# CAN.net
KiCad netlist of a schematic drawn in Altium Designer
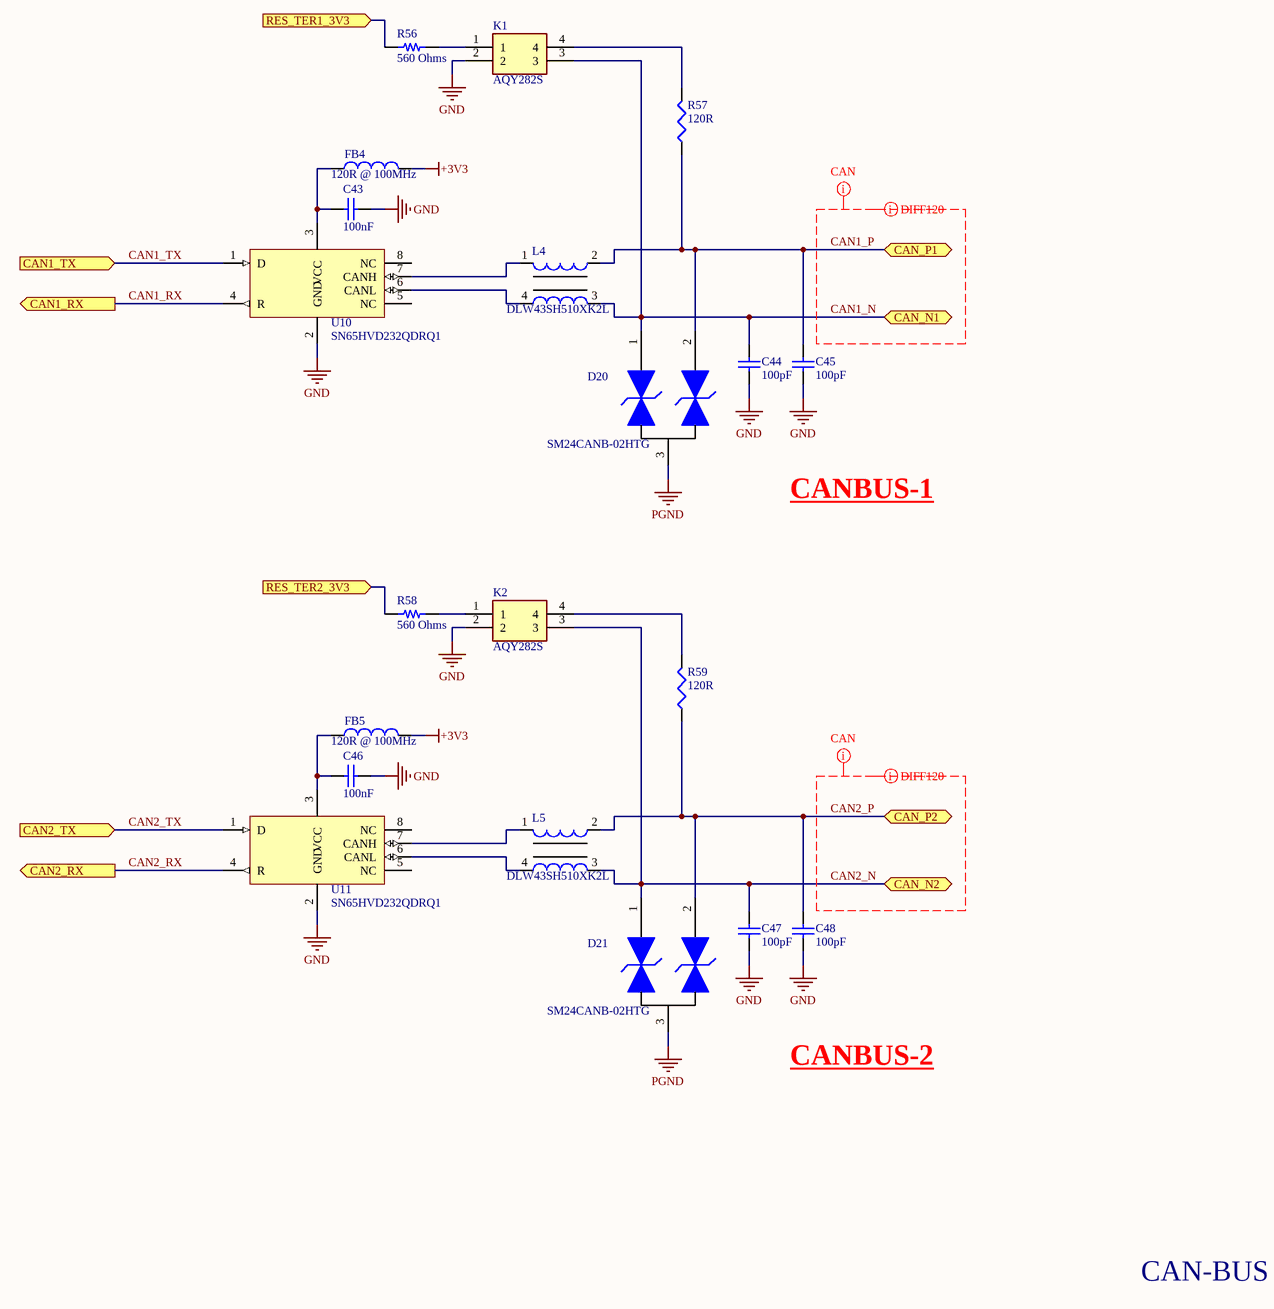
[diagram p0: CAN.SchDoc]

(export (version "E")
  (design (tool "Eeschema 10.0.6"))
  (components
    (comp (ref "C43")
      (value "100nF")
      (footprint "CAP0603")
      (description "CAP CER 0.1UF 50V X7R 0603")
      (libsource (lib "CAP_Library") (part "CAP0603_100nF"))
    )
    (comp (ref "C44")
      (value "100pF")
      (footprint "CAP0603")
      (description "CAP CER 100PF 50V C0G/NP0 0603")
      (libsource (lib "CAP_Library") (part "CAP0603_100pF"))
    )
    (comp (ref "C45")
      (value "100pF")
      (footprint "CAP0603")
      (description "CAP CER 100PF 50V C0G/NP0 0603")
      (libsource (lib "CAP_Library") (part "CAP0603_100pF"))
    )
    (comp (ref "C46")
      (value "100nF")
      (footprint "CAP0603")
      (description "CAP CER 0.1UF 50V X7R 0603")
      (libsource (lib "CAP_Library") (part "CAP0603_100nF"))
    )
    (comp (ref "C47")
      (value "100pF")
      (footprint "CAP0603")
      (description "CAP CER 100PF 50V C0G/NP0 0603")
      (libsource (lib "CAP_Library") (part "CAP0603_100pF"))
    )
    (comp (ref "C48")
      (value "100pF")
      (footprint "CAP0603")
      (description "CAP CER 100PF 50V C0G/NP0 0603")
      (libsource (lib "CAP_Library") (part "CAP0603_100pF"))
    )
    (comp (ref "D20")
      (value "CAN")
      (footprint "SOT23_3-DIODE")
      (description "TVS DIODE 24VWM 50VC SOT23-3")
      (fields (field (name "P/N") "SM24CANB-02HTG"))
      (libsource (lib "DIODE_Library") (part "SM24CANB-02HTG_TVS"))
    )
    (comp (ref "D21")
      (value "CAN")
      (footprint "SOT23_3-DIODE")
      (description "TVS DIODE 24VWM 50VC SOT23-3")
      (fields (field (name "P/N") "SM24CANB-02HTG"))
      (libsource (lib "DIODE_Library") (part "SM24CANB-02HTG_TVS"))
    )
    (comp (ref "FB4")
      (value "120R @ 100MHz")
      (footprint "FB0603")
      (description "FERRITE BEAD 120 OHM 0603 1LN")
      (libsource (lib "FB_Library") (part "FB0603_120R@100MHz"))
    )
    (comp (ref "FB5")
      (value "120R @ 100MHz")
      (footprint "FB0603")
      (description "FERRITE BEAD 120 OHM 0603 1LN")
      (libsource (lib "FB_Library") (part "FB0603_120R@100MHz"))
    )
    (comp (ref "K1")
      (value "AQY282S")
      (footprint "SamacSys:SOP254P680X230-4N")
      (description "Relay or Contactor")
      (fields (field (name "MOUSER PART NUMBER") "769-AQY282S"))
      (libsource (lib "SamacSys") (part "AQY282S"))
    )
    (comp (ref "K2")
      (value "AQY282S")
      (footprint "SamacSys:SOP254P680X230-4N")
      (description "Relay or Contactor")
      (fields (field (name "MOUSER PART NUMBER") "769-AQY282S"))
      (libsource (lib "SamacSys") (part "AQY282S"))
    )
    (comp (ref "L4")
      (value "CMC_DLW43SH510XK2L")
      (footprint "CMC_DLW43SH510XK2L")
      (description "CMC 51UH 230MA 2LN SMD AEC-Q200")
      (fields (field (name "P/N") "DLW43SH510XK2L"))
      (libsource (lib "IND_Library") (part "CMC_DLW43SH510XK2L"))
    )
    (comp (ref "L5")
      (value "CMC_DLW43SH510XK2L")
      (footprint "CMC_DLW43SH510XK2L")
      (description "CMC 51UH 230MA 2LN SMD AEC-Q200")
      (fields (field (name "P/N") "DLW43SH510XK2L"))
      (libsource (lib "IND_Library") (part "CMC_DLW43SH510XK2L"))
    )
    (comp (ref "R56")
      (value "560 Ohms")
      (footprint "RES 0603_1608")
      (description "RES 560 OHM 5% 1/10W 0603")
      (fields
        (field (name "PART NUMBER") "RMCF0603JT560R")
        (field (name "MANUFACTURER") "Stackpole Electronics Inc")
      )
      (libsource (lib "Celestial Altium Library") (part "Resistor"))
    )
    (comp (ref "R57")
      (value "120R")
      (footprint "RES0603")
      (description "RES SMD 120 OHM 1% 1/10W 0603")
      (libsource (lib "RES_Library") (part "RES0603_120R"))
    )
    (comp (ref "R58")
      (value "560 Ohms")
      (footprint "RES 0603_1608")
      (description "RES 560 OHM 5% 1/10W 0603")
      (fields
        (field (name "PART NUMBER") "RMCF0603JT560R")
        (field (name "MANUFACTURER") "Stackpole Electronics Inc")
      )
      (libsource (lib "Celestial Altium Library") (part "Resistor"))
    )
    (comp (ref "R59")
      (value "120R")
      (footprint "RES0603")
      (description "RES SMD 120 OHM 1% 1/10W 0603")
      (libsource (lib "RES_Library") (part "RES0603_120R"))
    )
    (comp (ref "U10")
      (value "CAN")
      (footprint "SOIC8")
      (description "IC TRANSCEIVER HALF 1/1 8SOIC")
      (fields (field (name "P/N") "SN65HVD232QDRQ1"))
      (libsource (lib "IC_Library") (part "SN65HVD232QDRQ1_CAN"))
    )
    (comp (ref "U11")
      (value "CAN")
      (footprint "SOIC8")
      (description "IC TRANSCEIVER HALF 1/1 8SOIC")
      (fields (field (name "P/N") "SN65HVD232QDRQ1"))
      (libsource (lib "IC_Library") (part "SN65HVD232QDRQ1_CAN"))
    )
  )
  (nets
    (net (code "1") (name "+3V3") (class "Default")
      (node (ref "FB4") (pin "2") (pinfunction "2_2") (pintype "passive"))
      (node (ref "FB5") (pin "2") (pinfunction "2_2") (pintype "passive"))
    )
    (net (code "2") (name "/CAN1_N") (class "Default")
      (node (ref "C44") (pin "2") (pinfunction "2_2") (pintype "passive"))
      (node (ref "D20") (pin "1") (pinfunction "1_1") (pintype "passive"))
      (node (ref "K1") (pin "3") (pinfunction "3_3") (pintype "passive"))
      (node (ref "L4") (pin "3") (pinfunction "3_3") (pintype "passive"))
    )
    (net (code "3") (name "/CAN1_P") (class "Default")
      (node (ref "C45") (pin "2") (pinfunction "2_2") (pintype "passive"))
      (node (ref "D20") (pin "2") (pinfunction "2_2") (pintype "passive"))
      (node (ref "L4") (pin "2") (pinfunction "2_2") (pintype "passive"))
      (node (ref "R57") (pin "1") (pinfunction "1_1") (pintype "passive"))
    )
    (net (code "4") (name "/CAN1_RX") (class "Default")
      (node (ref "U10") (pin "4") (pinfunction "R_4") (pintype "output"))
    )
    (net (code "5") (name "/CAN1_TX") (class "Default")
      (node (ref "U10") (pin "1") (pinfunction "D_1") (pintype "input"))
    )
    (net (code "6") (name "/CAN2_N") (class "Default")
      (node (ref "C47") (pin "2") (pinfunction "2_2") (pintype "passive"))
      (node (ref "D21") (pin "1") (pinfunction "1_1") (pintype "passive"))
      (node (ref "K2") (pin "3") (pinfunction "3_3") (pintype "passive"))
      (node (ref "L5") (pin "3") (pinfunction "3_3") (pintype "passive"))
    )
    (net (code "7") (name "/CAN2_P") (class "Default")
      (node (ref "C48") (pin "2") (pinfunction "2_2") (pintype "passive"))
      (node (ref "D21") (pin "2") (pinfunction "2_2") (pintype "passive"))
      (node (ref "L5") (pin "2") (pinfunction "2_2") (pintype "passive"))
      (node (ref "R59") (pin "1") (pinfunction "1_1") (pintype "passive"))
    )
    (net (code "8") (name "/CAN2_RX") (class "Default")
      (node (ref "U11") (pin "4") (pinfunction "R_4") (pintype "output"))
    )
    (net (code "9") (name "/CAN2_TX") (class "Default")
      (node (ref "U11") (pin "1") (pinfunction "D_1") (pintype "input"))
    )
    (net (code "10") (name "/RES_TER1_3V3") (class "Default")
      (node (ref "R56") (pin "1") (pinfunction "1_1") (pintype "passive"))
    )
    (net (code "11") (name "/RES_TER2_3V3") (class "Default")
      (node (ref "R58") (pin "1") (pinfunction "1_1") (pintype "passive"))
    )
    (net (code "12") (name "GND") (class "Default")
      (node (ref "C43") (pin "2") (pinfunction "2_2") (pintype "passive"))
      (node (ref "C44") (pin "1") (pinfunction "1_1") (pintype "passive"))
      (node (ref "C45") (pin "1") (pinfunction "1_1") (pintype "passive"))
      (node (ref "C46") (pin "2") (pinfunction "2_2") (pintype "passive"))
      (node (ref "C47") (pin "1") (pinfunction "1_1") (pintype "passive"))
      (node (ref "C48") (pin "1") (pinfunction "1_1") (pintype "passive"))
      (node (ref "K1") (pin "2") (pinfunction "2_2") (pintype "passive"))
      (node (ref "K2") (pin "2") (pinfunction "2_2") (pintype "passive"))
      (node (ref "U10") (pin "2") (pinfunction "GND_2") (pintype "passive"))
      (node (ref "U11") (pin "2") (pinfunction "GND_2") (pintype "passive"))
    )
    (net (code "13") (name "Net-(K1-Pad1)") (class "Default")
      (node (ref "K1") (pin "1") (pinfunction "1_1") (pintype "passive"))
      (node (ref "R56") (pin "2") (pinfunction "2_2") (pintype "passive"))
    )
    (net (code "14") (name "Net-(K1-Pad4)") (class "Default")
      (node (ref "K1") (pin "4") (pinfunction "4_4") (pintype "passive"))
      (node (ref "R57") (pin "2") (pinfunction "2_2") (pintype "passive"))
    )
    (net (code "15") (name "Net-(K2-Pad1)") (class "Default")
      (node (ref "K2") (pin "1") (pinfunction "1_1") (pintype "passive"))
      (node (ref "R58") (pin "2") (pinfunction "2_2") (pintype "passive"))
    )
    (net (code "16") (name "Net-(K2-Pad4)") (class "Default")
      (node (ref "K2") (pin "4") (pinfunction "4_4") (pintype "passive"))
      (node (ref "R59") (pin "2") (pinfunction "2_2") (pintype "passive"))
    )
    (net (code "17") (name "Net-(U10-CANH)") (class "Default")
      (node (ref "L4") (pin "1") (pinfunction "1_1") (pintype "passive"))
      (node (ref "U10") (pin "7") (pinfunction "CANH_7") (pintype "bidirectional"))
    )
    (net (code "18") (name "Net-(U10-CANL)") (class "Default")
      (node (ref "L4") (pin "4") (pinfunction "4_4") (pintype "passive"))
      (node (ref "U10") (pin "6") (pinfunction "CANL_6") (pintype "bidirectional"))
    )
    (net (code "19") (name "Net-(U10-VCC)") (class "Default")
      (node (ref "C43") (pin "1") (pinfunction "1_1") (pintype "passive"))
      (node (ref "FB4") (pin "1") (pinfunction "1_1") (pintype "passive"))
      (node (ref "U10") (pin "3") (pinfunction "VCC_3") (pintype "passive"))
    )
    (net (code "20") (name "Net-(U11-CANH)") (class "Default")
      (node (ref "L5") (pin "1") (pinfunction "1_1") (pintype "passive"))
      (node (ref "U11") (pin "7") (pinfunction "CANH_7") (pintype "bidirectional"))
    )
    (net (code "21") (name "Net-(U11-CANL)") (class "Default")
      (node (ref "L5") (pin "4") (pinfunction "4_4") (pintype "passive"))
      (node (ref "U11") (pin "6") (pinfunction "CANL_6") (pintype "bidirectional"))
    )
    (net (code "22") (name "Net-(U11-VCC)") (class "Default")
      (node (ref "C46") (pin "1") (pinfunction "1_1") (pintype "passive"))
      (node (ref "FB5") (pin "1") (pinfunction "1_1") (pintype "passive"))
      (node (ref "U11") (pin "3") (pinfunction "VCC_3") (pintype "passive"))
    )
    (net (code "23") (name "PGND") (class "Default")
      (node (ref "D20") (pin "3") (pinfunction "3_3") (pintype "passive"))
      (node (ref "D21") (pin "3") (pinfunction "3_3") (pintype "passive"))
    )
    (net (code "24") (name "unconnected-(U10-NC-Pad5)") (class "Default")
      (node (ref "U10") (pin "5") (pinfunction "NC_5") (pintype "passive"))
    )
    (net (code "25") (name "unconnected-(U10-NC-Pad8)") (class "Default")
      (node (ref "U10") (pin "8") (pinfunction "NC_8") (pintype "passive"))
    )
    (net (code "26") (name "unconnected-(U11-NC-Pad5)") (class "Default")
      (node (ref "U11") (pin "5") (pinfunction "NC_5") (pintype "passive"))
    )
    (net (code "27") (name "unconnected-(U11-NC-Pad8)") (class "Default")
      (node (ref "U11") (pin "8") (pinfunction "NC_8") (pintype "passive"))
    )
  )
)
